# tweeq-Stamp_RTC_DS1337.net
KiCad netlist of a schematic drawn in EAGLE
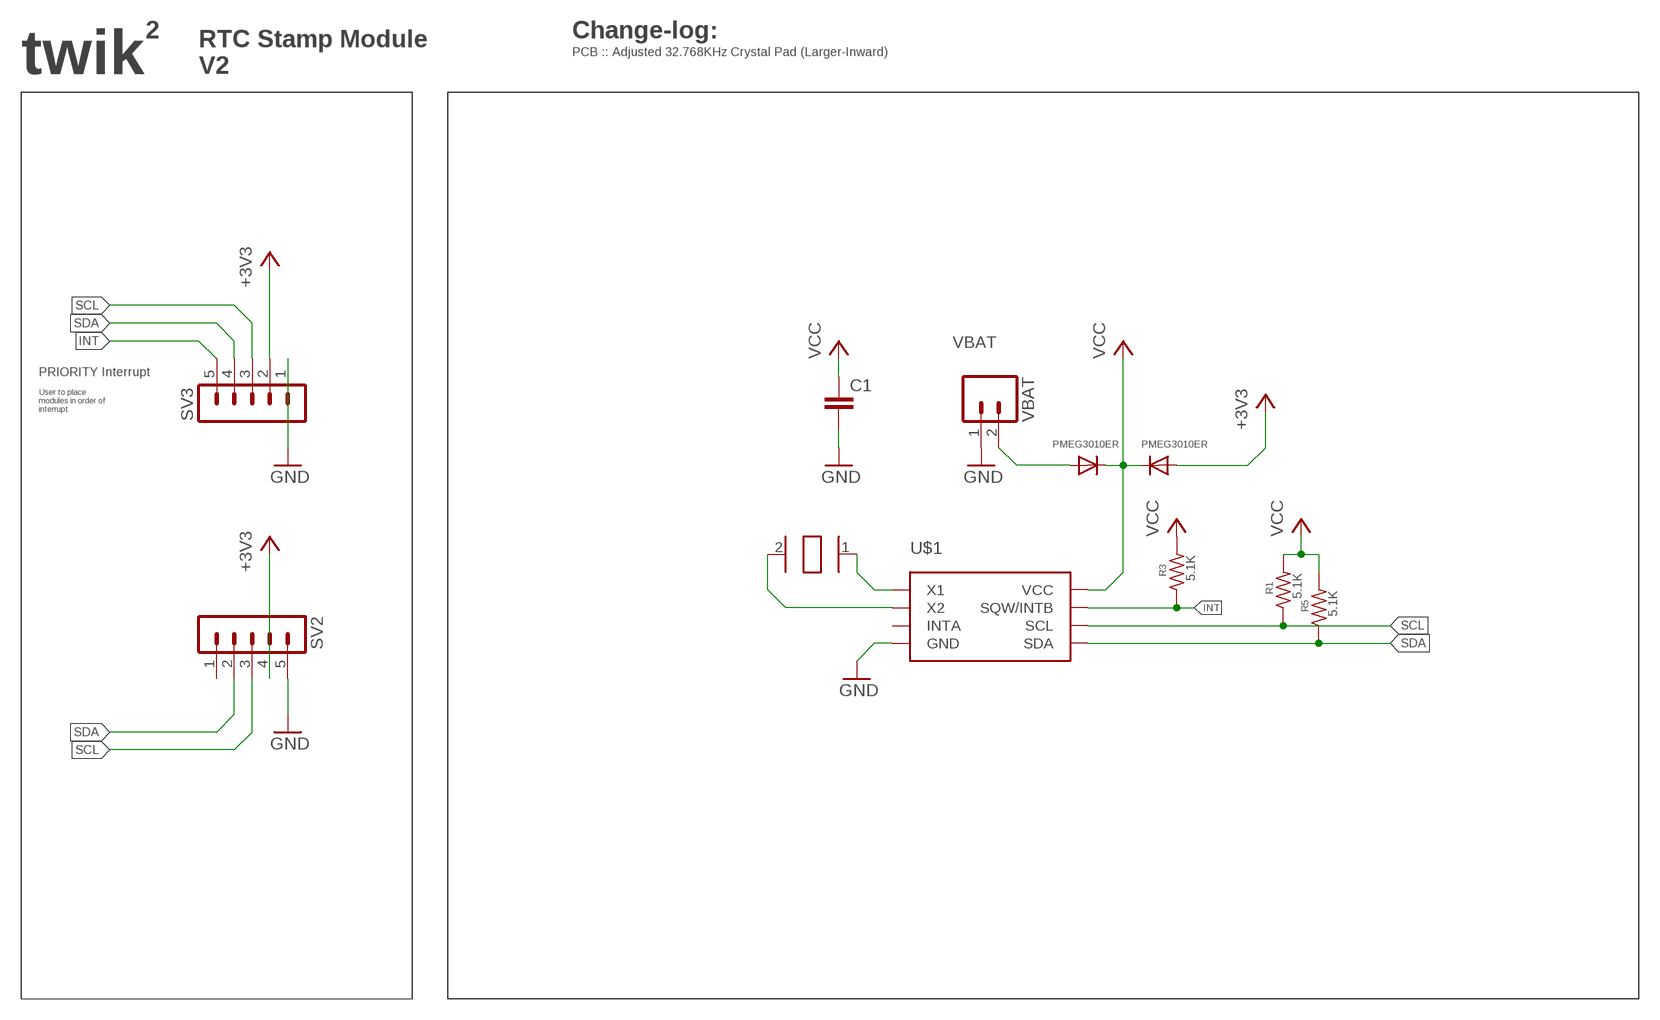
[diagram p0: schematic, sheet 1]

(export (version "E")
  (design (tool "Eeschema 10.0.6"))
  (components
    (comp (ref "C1")
      (value "C-EUC0402K")
      (footprint "eagle-import:C0402K")
      (libsource (lib "eagle-import") (part "C-EUC0402K"))
    )
    (comp (ref "R1")
      (value "5.1K")
      (footprint "eagle-import:R0402")
      (libsource (lib "eagle-import") (part "R-US_R0402"))
    )
    (comp (ref "R3")
      (value "5.1K")
      (footprint "eagle-import:R0402")
      (libsource (lib "eagle-import") (part "R-US_R0402"))
    )
    (comp (ref "R5")
      (value "5.1K")
      (footprint "eagle-import:R0402")
      (libsource (lib "eagle-import") (part "R-US_R0402"))
    )
    (comp (ref "SV2")
      (value "M05-1STAMP")
      (footprint "eagle-import:1X05-1.5MM-STAMP")
      (libsource (lib "eagle-import") (part "M05-1STAMP"))
    )
    (comp (ref "SV3")
      (value "M05-1STAMP")
      (footprint "eagle-import:1X05-1.5MM-STAMP")
      (libsource (lib "eagle-import") (part "M05-1STAMP"))
    )
    (comp (ref "U$1")
      (value "DS1337SO")
      (footprint "eagle-import:MSOP8")
      (libsource (lib "eagle-import") (part "DS1337SO"))
    )
    (comp (ref "U$2")
      (value "32.765KHZ_CRYSTALABS07")
      (footprint "eagle-import:ABS07")
      (libsource (lib "eagle-import") (part "32.765KHZ_CRYSTALABS07"))
    )
    (comp (ref "U$4")
      (value "PMEG3010ER/MOD")
      (footprint "eagle-import:SOD123-MOD")
      (libsource (lib "eagle-import") (part "PMEG3010ER/MOD"))
    )
    (comp (ref "U$6")
      (value "PMEG3010ER/MOD")
      (footprint "eagle-import:SOD123-MOD")
      (libsource (lib "eagle-import") (part "PMEG3010ER/MOD"))
    )
    (comp (ref "VBAT")
      (value "M021X02_SMD_SQUARE")
      (footprint "eagle-import:1X02_SMD")
      (libsource (lib "eagle-import") (part "M021X02_SMD_SQUARE"))
    )
  )
  (nets
    (net (code "1") (name "+3V3") (class "Default")
      (node (ref "SV2") (pin "4") (pinfunction "4_4") (pintype "passive"))
      (node (ref "SV3") (pin "2") (pinfunction "2_2") (pintype "passive"))
      (node (ref "U$6") (pin "A") (pinfunction "A_A") (pintype "passive"))
    )
    (net (code "2") (name "GND") (class "Default")
      (node (ref "C1") (pin "2") (pinfunction "2_2") (pintype "passive"))
      (node (ref "SV2") (pin "5") (pinfunction "5_5") (pintype "passive"))
      (node (ref "SV3") (pin "1") (pinfunction "1_1") (pintype "passive"))
      (node (ref "U$1") (pin "4") (pinfunction "GND_4") (pintype "bidirectional"))
      (node (ref "VBAT") (pin "1") (pinfunction "1_1") (pintype "passive"))
    )
    (net (code "3") (name "INT") (class "Default")
      (node (ref "R3") (pin "1") (pinfunction "1_1") (pintype "passive"))
      (node (ref "SV3") (pin "5") (pinfunction "5_5") (pintype "passive"))
      (node (ref "U$1") (pin "7") (pinfunction "SQW/INTB_7") (pintype "bidirectional"))
    )
    (net (code "4") (name "Net-(U$1-X1)") (class "Default")
      (node (ref "U$1") (pin "1") (pinfunction "X1_1") (pintype "bidirectional"))
      (node (ref "U$2") (pin "1") (pinfunction "P$1_1") (pintype "bidirectional"))
    )
    (net (code "5") (name "Net-(U$1-X2)") (class "Default")
      (node (ref "U$1") (pin "2") (pinfunction "X2_2") (pintype "bidirectional"))
      (node (ref "U$2") (pin "2") (pinfunction "P$2_2") (pintype "bidirectional"))
    )
    (net (code "6") (name "Net-(U$4-PadA)") (class "Default")
      (node (ref "U$4") (pin "A") (pinfunction "A_A") (pintype "passive"))
      (node (ref "VBAT") (pin "2") (pinfunction "2_2") (pintype "passive"))
    )
    (net (code "7") (name "SCL") (class "Default")
      (node (ref "R1") (pin "1") (pinfunction "1_1") (pintype "passive"))
      (node (ref "SV2") (pin "3") (pinfunction "3_3") (pintype "passive"))
      (node (ref "SV3") (pin "3") (pinfunction "3_3") (pintype "passive"))
      (node (ref "U$1") (pin "6") (pinfunction "SCL_6") (pintype "bidirectional"))
    )
    (net (code "8") (name "SDA") (class "Default")
      (node (ref "R5") (pin "1") (pinfunction "1_1") (pintype "passive"))
      (node (ref "SV2") (pin "2") (pinfunction "2_2") (pintype "passive"))
      (node (ref "SV3") (pin "4") (pinfunction "4_4") (pintype "passive"))
      (node (ref "U$1") (pin "5") (pinfunction "SDA_5") (pintype "bidirectional"))
    )
    (net (code "9") (name "VCC") (class "Default")
      (node (ref "C1") (pin "1") (pinfunction "1_1") (pintype "passive"))
      (node (ref "R1") (pin "2") (pinfunction "2_2") (pintype "passive"))
      (node (ref "R3") (pin "2") (pinfunction "2_2") (pintype "passive"))
      (node (ref "R5") (pin "2") (pinfunction "2_2") (pintype "passive"))
      (node (ref "U$1") (pin "8") (pinfunction "VCC_8") (pintype "bidirectional"))
      (node (ref "U$4") (pin "C") (pinfunction "C_C") (pintype "passive"))
      (node (ref "U$6") (pin "C") (pinfunction "C_C") (pintype "passive"))
    )
    (net (code "10") (name "unconnected-(SV2-Pad1)") (class "Default")
      (node (ref "SV2") (pin "1") (pinfunction "1_1") (pintype "passive"))
    )
    (net (code "11") (name "unconnected-(U$1-INTA-Pad3)") (class "Default")
      (node (ref "U$1") (pin "3") (pinfunction "INTA_3") (pintype "bidirectional"))
    )
  )
)
